# schematics.net
KiCad netlist of a schematic drawn in EAGLE
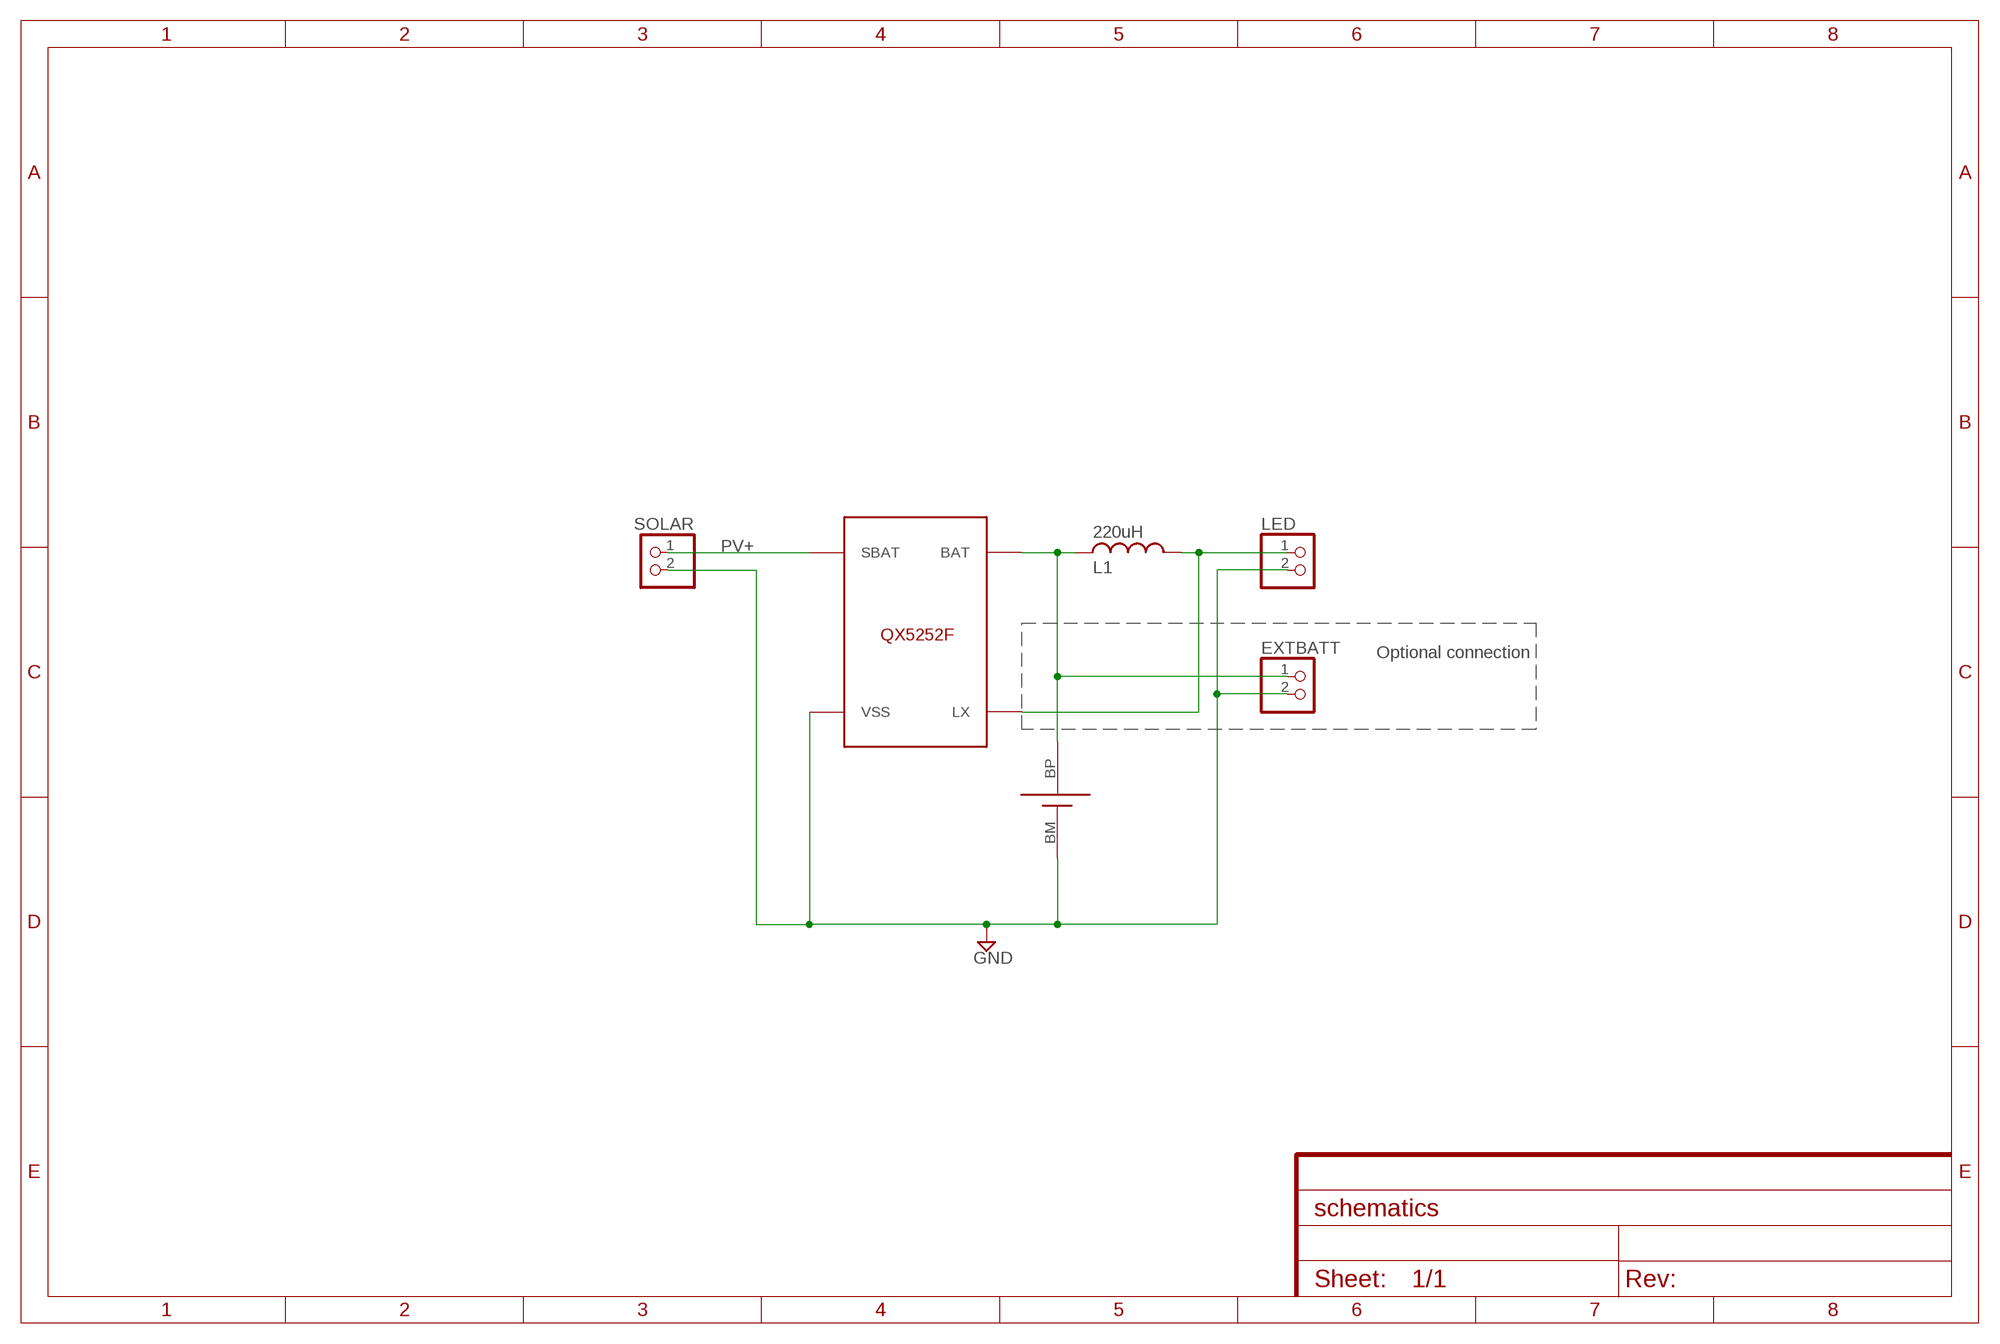
[diagram p0: schematic, sheet 1]

(export (version "E")
  (design (tool "Eeschema 10.0.6"))
  (components
    (comp (ref "EXTBATT")
      (value "PINHD-1X2")
      (footprint "eagle-import:1X02")
      (libsource (lib "eagle-import") (part "PINHD-1X2"))
    )
    (comp (ref "L1")
      (value "220uH")
      (footprint "eagle-import:0204_7")
      (libsource (lib "eagle-import") (part "L-US0204/7"))
    )
    (comp (ref "LED")
      (value "PINHD-1X2")
      (footprint "eagle-import:1X02")
      (libsource (lib "eagle-import") (part "PINHD-1X2"))
    )
    (comp (ref "SOLAR")
      (value "PINHD-1X2")
      (footprint "eagle-import:1X02")
      (libsource (lib "eagle-import") (part "PINHD-1X2"))
    )
    (comp (ref "U$1")
      (value "QX5252F")
      (footprint "eagle-import:TO-94")
      (libsource (lib "eagle-import") (part "QX5252F"))
    )
    (comp (ref "U$2")
      (value "NIMHCOINBAT")
      (footprint "eagle-import:12VNIMHBAT")
      (libsource (lib "eagle-import") (part "NIMHCOINBAT"))
    )
  )
  (nets
    (net (code "1") (name "/PV+") (class "Default")
      (node (ref "SOLAR") (pin "1") (pinfunction "1_1") (pintype "passive"))
      (node (ref "U$1") (pin "SBAT") (pinfunction "SBAT_SBAT") (pintype "input"))
    )
    (net (code "2") (name "GND") (class "Default")
      (node (ref "EXTBATT") (pin "2") (pinfunction "2_2") (pintype "passive"))
      (node (ref "LED") (pin "2") (pinfunction "2_2") (pintype "passive"))
      (node (ref "SOLAR") (pin "2") (pinfunction "2_2") (pintype "passive"))
      (node (ref "U$1") (pin "VSS") (pinfunction "VSS_VSS") (pintype "input"))
      (node (ref "U$2") (pin "BM") (pinfunction "GND_BM") (pintype "power_in"))
    )
    (net (code "3") (name "Net-(L1-Pad1)") (class "Default")
      (node (ref "L1") (pin "1") (pinfunction "1_1") (pintype "passive"))
      (node (ref "LED") (pin "1") (pinfunction "1_1") (pintype "passive"))
      (node (ref "U$1") (pin "LX") (pinfunction "LX_LX") (pintype "input"))
    )
    (net (code "4") (name "Net-(U$2-VCC)") (class "Default")
      (node (ref "EXTBATT") (pin "1") (pinfunction "1_1") (pintype "passive"))
      (node (ref "L1") (pin "2") (pinfunction "2_2") (pintype "passive"))
      (node (ref "U$1") (pin "BAT") (pinfunction "BAT_BAT") (pintype "output"))
      (node (ref "U$2") (pin "BP") (pinfunction "VCC_BP") (pintype "power_in"))
    )
  )
)
